# Amp.net
KiCad netlist of a schematic drawn in Altium Designer
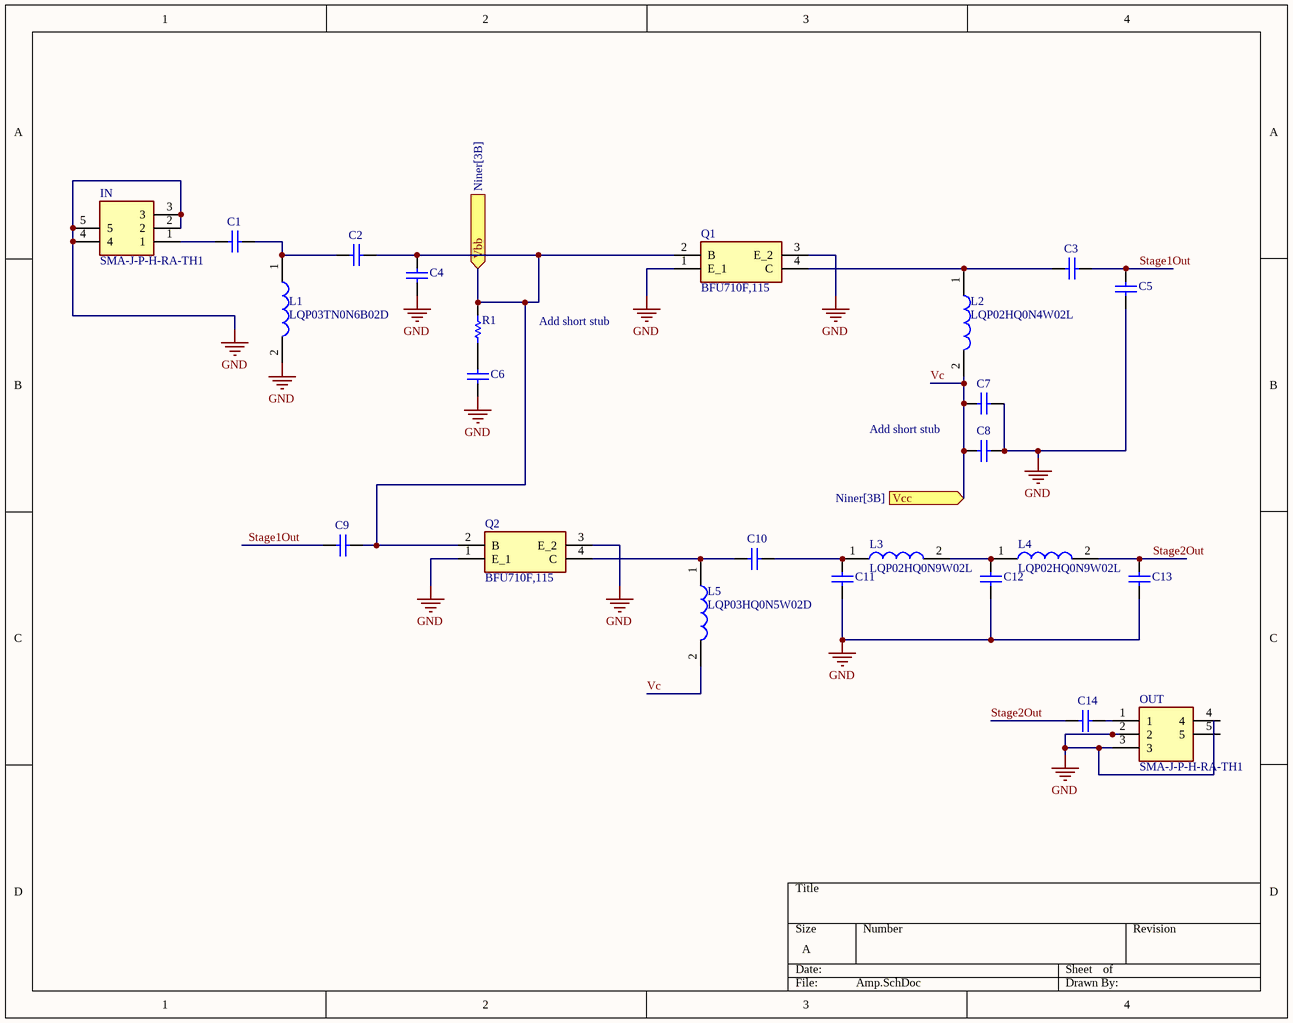
[diagram p0: Amp.SchDoc]

(export (version "E")
  (design (tool "Eeschema 10.0.6"))
  (components
    (comp (ref "C1")
      (value "QSCF500Q0R7B1GV001T")
      (footprint "JT_0402")
      (libsource (lib "MXLab Generic") (part "Capacitor Ceramic"))
    )
    (comp (ref "C2")
      (value "GQM1555C2DR60WB01D")
      (footprint "JT_0402")
      (libsource (lib "MXLab Generic") (part "Capacitor Ceramic"))
    )
    (comp (ref "C3")
      (value "GQM1555C2DR40WB01")
      (footprint "JT_0402")
      (libsource (lib "MXLab Generic") (part "Capacitor Ceramic"))
    )
    (comp (ref "C4")
      (value "GQM1555C2DR40WB01")
      (footprint "JT_0402")
      (libsource (lib "MXLab Generic") (part "Capacitor Ceramic"))
    )
    (comp (ref "C5")
      (value "GQM1555C2DR40WB01")
      (footprint "JT_0402")
      (libsource (lib "MXLab Generic") (part "Capacitor Ceramic"))
    )
    (comp (ref "C6")
      (value "GCQ0335C1HR60WB01D")
      (footprint "0402")
      (libsource (lib "MXLab Generic") (part "Capacitor Ceramic"))
    )
    (comp (ref "C7")
      (value "GCQ0335C1HR60WB01D")
      (footprint "0402")
      (libsource (lib "MXLab Generic") (part "Capacitor Ceramic"))
    )
    (comp (ref "C8")
      (value "GCQ0335C1HR60WB01D")
      (footprint "0402")
      (libsource (lib "MXLab Generic") (part "Capacitor Ceramic"))
    )
    (comp (ref "C9")
      (value "QSCF500Q0R7B1GV001T")
      (footprint "JT_0402")
      (libsource (lib "MXLab Generic") (part "Capacitor Ceramic"))
    )
    (comp (ref "C10")
      (value "GQM1555C2DR70WB01")
      (footprint "JT_0402")
      (libsource (lib "MXLab Generic") (part "Capacitor Ceramic"))
    )
    (comp (ref "C11")
      (value "GQM1555C2DR40WB01")
      (footprint "JT_0402")
      (libsource (lib "MXLab Generic") (part "Capacitor Ceramic"))
    )
    (comp (ref "C12")
      (value "GQM1555C2DR60WB01D")
      (footprint "JT_0402")
      (libsource (lib "MXLab Generic") (part "Capacitor Ceramic"))
    )
    (comp (ref "C13")
      (value "GQM1555C2DR40WB01")
      (footprint "JT_0402")
      (libsource (lib "MXLab Generic") (part "Capacitor Ceramic"))
    )
    (comp (ref "C14")
      (value "QSCF500Q0R7B1GV001T")
      (footprint "JT_0402")
      (libsource (lib "MXLab Generic") (part "Capacitor Ceramic"))
    )
    (comp (ref "IN")
      (value "SMA-J-P-H-RA-TH1")
      (footprint "Footprints:SMAJPHRATH1")
      (description "Connector")
      (fields (field (name "MOUSER PART NUMBER") "200-SMAJPHRATH1"))
      (libsource (lib "Components") (part "SMA-J-P-H-RA-TH1"))
    )
    (comp (ref "L1")
      (value "LQP03TN0N6B02D")
      (footprint "Footprints:LQP03TG3N1B02D")
      (description "Inductor")
      (fields (field (name "MOUSER PART NUMBER") "81-LQP03TN0N6B02D"))
      (libsource (lib "*") (part "LQP03TN0N6B02D"))
    )
    (comp (ref "L2")
      (value "LQP02HQ0N4W02L")
      (footprint "Footprints:LQP02HQ0N2B02E")
      (description "Inductor")
      (fields (field (name "MOUSER PART NUMBER") "81-LQP02HQ0N4W02L"))
      (libsource (lib "*") (part "LQP02HQ0N4W02L"))
    )
    (comp (ref "L3")
      (value "LQP02HQ0N9W02L")
      (footprint "Footprints:LQP02HQ0N2B02E")
      (description "Inductor")
      (fields (field (name "MOUSER PART NUMBER") "81-LQP02HQ0N9W02L"))
      (libsource (lib "*") (part "LQP02HQ0N9W02L"))
    )
    (comp (ref "L4")
      (value "LQP02HQ0N9W02L")
      (footprint "Footprints:LQP02HQ0N2B02E")
      (description "Inductor")
      (fields (field (name "MOUSER PART NUMBER") "81-LQP02HQ0N9W02L"))
      (libsource (lib "*") (part "LQP02HQ0N9W02L"))
    )
    (comp (ref "L5")
      (value "LQP03HQ0N5W02D")
      (footprint "Footprints:LQP03HQ0N5B02D")
      (description "Inductor")
      (fields (field (name "MOUSER PART NUMBER") "81-LQP03HQ0N5W02D"))
      (libsource (lib "Components") (part "LQP03HQ0N5W02D"))
    )
    (comp (ref "OUT")
      (value "SMA-J-P-H-RA-TH1")
      (footprint "Footprints:SMAJPHRATH1")
      (description "Connector")
      (fields (field (name "MOUSER PART NUMBER") "200-SMAJPHRATH1"))
      (libsource (lib "") (part "SMA-J-P-H-RA-TH1_1"))
    )
    (comp (ref "Q1")
      (value "BFU710F,115")
      (footprint "Footprints:BFU710F115")
      (description "Transistor BJT NPN")
      (fields (field (name "MOUSER PART NUMBER") "771-BFU710F115"))
      (libsource (lib "*") (part "BFU710F,115"))
    )
    (comp (ref "Q2")
      (value "BFU710F,115")
      (footprint "Footprints:BFU710F115")
      (description "Transistor BJT NPN")
      (fields (field (name "MOUSER PART NUMBER") "771-BFU710F115"))
      (libsource (lib "*") (part "BFU710F,115"))
    )
    (comp (ref "R1")
      (value "Resistor")
      (footprint "0402")
      (description "Resistive element")
      (libsource (lib "MXLab Generic") (part "Resistor"))
    )
  )
  (nets
    (net (code "1") (name "/Stage1Out") (class "Default")
      (node (ref "C3") (pin "2") (pinfunction "2_2") (pintype "passive"))
      (node (ref "C5") (pin "2") (pinfunction "2_2") (pintype "passive"))
      (node (ref "C9") (pin "2") (pinfunction "2_2") (pintype "passive"))
    )
    (net (code "2") (name "/Stage2Out") (class "Default")
      (node (ref "C13") (pin "2") (pinfunction "2_2") (pintype "passive"))
      (node (ref "C14") (pin "2") (pinfunction "2_2") (pintype "passive"))
      (node (ref "L4") (pin "2") (pinfunction "2_2") (pintype "passive"))
    )
    (net (code "3") (name "/Vbb") (class "Default")
      (node (ref "C2") (pin "1") (pinfunction "1_1") (pintype "passive"))
      (node (ref "C4") (pin "1") (pinfunction "1_1") (pintype "passive"))
      (node (ref "C9") (pin "1") (pinfunction "1_1") (pintype "passive"))
      (node (ref "Q1") (pin "2") (pinfunction "B_2") (pintype "passive"))
      (node (ref "Q2") (pin "2") (pinfunction "B_2") (pintype "passive"))
      (node (ref "R1") (pin "2") (pinfunction "2_2") (pintype "passive"))
    )
    (net (code "4") (name "/Vc") (class "Default")
      (node (ref "C7") (pin "2") (pinfunction "2_2") (pintype "passive"))
      (node (ref "C8") (pin "2") (pinfunction "2_2") (pintype "passive"))
      (node (ref "L2") (pin "2") (pinfunction "2_2") (pintype "passive"))
      (node (ref "L5") (pin "2") (pinfunction "2_2") (pintype "passive"))
    )
    (net (code "5") (name "GND") (class "Default")
      (node (ref "C11") (pin "1") (pinfunction "1_1") (pintype "passive"))
      (node (ref "C12") (pin "2") (pinfunction "2_2") (pintype "passive"))
      (node (ref "C13") (pin "1") (pinfunction "1_1") (pintype "passive"))
      (node (ref "C4") (pin "2") (pinfunction "2_2") (pintype "passive"))
      (node (ref "C5") (pin "1") (pinfunction "1_1") (pintype "passive"))
      (node (ref "C6") (pin "1") (pinfunction "1_1") (pintype "passive"))
      (node (ref "C7") (pin "1") (pinfunction "1_1") (pintype "passive"))
      (node (ref "C8") (pin "1") (pinfunction "1_1") (pintype "passive"))
      (node (ref "IN") (pin "2") (pinfunction "2_2") (pintype "passive"))
      (node (ref "IN") (pin "3") (pinfunction "3_3") (pintype "passive"))
      (node (ref "IN") (pin "4") (pinfunction "4_4") (pintype "passive"))
      (node (ref "IN") (pin "5") (pinfunction "5_5") (pintype "passive"))
      (node (ref "L1") (pin "2") (pinfunction "2_2") (pintype "passive"))
      (node (ref "OUT") (pin "2") (pinfunction "2_2") (pintype "passive"))
      (node (ref "OUT") (pin "3") (pinfunction "3_3") (pintype "passive"))
      (node (ref "Q1") (pin "1") (pinfunction "E_1_1") (pintype "passive"))
      (node (ref "Q1") (pin "3") (pinfunction "E_2_3") (pintype "passive"))
      (node (ref "Q2") (pin "1") (pinfunction "E_1_1") (pintype "passive"))
      (node (ref "Q2") (pin "3") (pinfunction "E_2_3") (pintype "passive"))
    )
    (net (code "6") (name "Net-(C1-Pad1)") (class "Default")
      (node (ref "C1") (pin "1") (pinfunction "1_1") (pintype "passive"))
      (node (ref "C2") (pin "2") (pinfunction "2_2") (pintype "passive"))
      (node (ref "L1") (pin "1") (pinfunction "1_1") (pintype "passive"))
    )
    (net (code "7") (name "Net-(C1-Pad2)") (class "Default")
      (node (ref "C1") (pin "2") (pinfunction "2_2") (pintype "passive"))
      (node (ref "IN") (pin "1") (pinfunction "1_1") (pintype "passive"))
    )
    (net (code "8") (name "Net-(C6-Pad2)") (class "Default")
      (node (ref "C6") (pin "2") (pinfunction "2_2") (pintype "passive"))
      (node (ref "R1") (pin "1") (pinfunction "1_1") (pintype "passive"))
    )
    (net (code "9") (name "Net-(C10-Pad1)") (class "Default")
      (node (ref "C10") (pin "1") (pinfunction "1_1") (pintype "passive"))
      (node (ref "C11") (pin "2") (pinfunction "2_2") (pintype "passive"))
      (node (ref "L3") (pin "1") (pinfunction "1_1") (pintype "passive"))
    )
    (net (code "10") (name "Net-(C12-Pad1)") (class "Default")
      (node (ref "C12") (pin "1") (pinfunction "1_1") (pintype "passive"))
      (node (ref "L3") (pin "2") (pinfunction "2_2") (pintype "passive"))
      (node (ref "L4") (pin "1") (pinfunction "1_1") (pintype "passive"))
    )
    (net (code "11") (name "Net-(C14-Pad1)") (class "Default")
      (node (ref "C14") (pin "1") (pinfunction "1_1") (pintype "passive"))
      (node (ref "OUT") (pin "1") (pinfunction "1_1") (pintype "passive"))
    )
    (net (code "12") (name "Net-(Q1-C)") (class "Default")
      (node (ref "C3") (pin "1") (pinfunction "1_1") (pintype "passive"))
      (node (ref "L2") (pin "1") (pinfunction "1_1") (pintype "passive"))
      (node (ref "Q1") (pin "4") (pinfunction "C_4") (pintype "passive"))
    )
    (net (code "13") (name "Net-(Q2-C)") (class "Default")
      (node (ref "C10") (pin "2") (pinfunction "2_2") (pintype "passive"))
      (node (ref "L5") (pin "1") (pinfunction "1_1") (pintype "passive"))
      (node (ref "Q2") (pin "4") (pinfunction "C_4") (pintype "passive"))
    )
    (net (code "14") (name "unconnected-(OUT-Pad4)") (class "Default")
      (node (ref "OUT") (pin "4") (pinfunction "4_4") (pintype "passive"))
    )
    (net (code "15") (name "unconnected-(OUT-Pad5)") (class "Default")
      (node (ref "OUT") (pin "5") (pinfunction "5_5") (pintype "passive"))
    )
  )
)
